# untitled.net
KiCad netlist of a schematic drawn in EAGLE
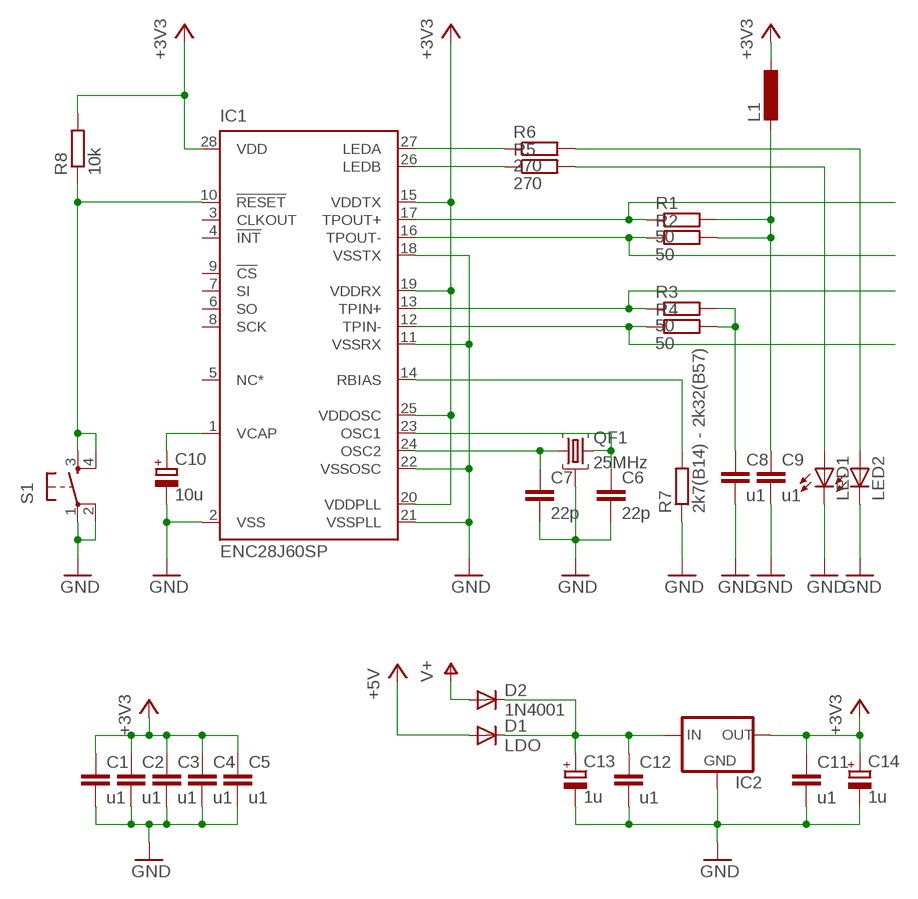
[diagram p0: schematic, sheet 1]

(export (version "E")
  (design (tool "Eeschema 10.0.6"))
  (components
    (comp (ref "C1")
      (value "u1")
      (footprint "eagle-import:C025-025X050")
      (libsource (lib "eagle-import") (part "C-EU025-025X050"))
    )
    (comp (ref "C2")
      (value "u1")
      (footprint "eagle-import:C025-025X050")
      (libsource (lib "eagle-import") (part "C-EU025-025X050"))
    )
    (comp (ref "C3")
      (value "u1")
      (footprint "eagle-import:C025-025X050")
      (libsource (lib "eagle-import") (part "C-EU025-025X050"))
    )
    (comp (ref "C4")
      (value "u1")
      (footprint "eagle-import:C025-025X050")
      (libsource (lib "eagle-import") (part "C-EU025-025X050"))
    )
    (comp (ref "C5")
      (value "u1")
      (footprint "eagle-import:C025-025X050")
      (libsource (lib "eagle-import") (part "C-EU025-025X050"))
    )
    (comp (ref "C6")
      (value "22p")
      (footprint "eagle-import:C025-025X050")
      (libsource (lib "eagle-import") (part "C-EU025-025X050"))
    )
    (comp (ref "C7")
      (value "22p")
      (footprint "eagle-import:C025-025X050")
      (libsource (lib "eagle-import") (part "C-EU025-025X050"))
    )
    (comp (ref "C8")
      (value "u1")
      (footprint "eagle-import:C025-025X050")
      (libsource (lib "eagle-import") (part "C-EU025-025X050"))
    )
    (comp (ref "C9")
      (value "u1")
      (footprint "eagle-import:C025-025X050")
      (libsource (lib "eagle-import") (part "C-EU025-025X050"))
    )
    (comp (ref "C10")
      (value "10u")
      (footprint "eagle-import:E2,5-6")
      (libsource (lib "eagle-import") (part "CPOL-EUE2.5-6"))
    )
    (comp (ref "C11")
      (value "u1")
      (footprint "eagle-import:C025-025X050")
      (libsource (lib "eagle-import") (part "C-EU025-025X050"))
    )
    (comp (ref "C12")
      (value "u1")
      (footprint "eagle-import:C025-025X050")
      (libsource (lib "eagle-import") (part "C-EU025-025X050"))
    )
    (comp (ref "C13")
      (value "1u")
      (footprint "eagle-import:E2,5-6")
      (libsource (lib "eagle-import") (part "CPOL-EUE2.5-6"))
    )
    (comp (ref "C14")
      (value "1u")
      (footprint "eagle-import:E2,5-6")
      (libsource (lib "eagle-import") (part "CPOL-EUE2.5-6"))
    )
    (comp (ref "D1")
      (value "LDO")
      (footprint "eagle-import:D-2.5")
      (libsource (lib "eagle-import") (part "DIODE-D-2.5"))
    )
    (comp (ref "D2")
      (value "1N4001")
      (footprint "eagle-import:D-2.5")
      (libsource (lib "eagle-import") (part "DIODE-D-2.5"))
    )
    (comp (ref "IC1")
      (value "ENC28J60SP")
      (footprint "eagle-import:DIL28-3")
      (fields (field (name "MF") "MICROCHIP") (field (name "MPN") "ENC28J60/SP"))
      (libsource (lib "eagle-import") (part "ENC28J60SP"))
    )
    (comp (ref "IC2")
      (value "MCP1700_TO92-INLINE")
      (footprint "eagle-import:TO92-")
      (libsource (lib "eagle-import") (part "MCP1700_TO92-INLINE"))
    )
    (comp (ref "L1")
      (value "L-EU0204/5")
      (footprint "eagle-import:0204_5")
      (libsource (lib "eagle-import") (part "L-EU0204/5"))
    )
    (comp (ref "LED1")
      (value "LED5MM")
      (footprint "eagle-import:LED5MM")
      (libsource (lib "eagle-import") (part "LED5MM"))
    )
    (comp (ref "LED2")
      (value "LED5MM")
      (footprint "eagle-import:LED5MM")
      (libsource (lib "eagle-import") (part "LED5MM"))
    )
    (comp (ref "QF1")
      (value "25MHz")
      (footprint "eagle-import:HC49U")
      (libsource (lib "eagle-import") (part "8M10AHC49T"))
    )
    (comp (ref "R1")
      (value "50")
      (footprint "eagle-import:0204_7")
      (libsource (lib "eagle-import") (part "R-EU_0204/7"))
    )
    (comp (ref "R2")
      (value "50")
      (footprint "eagle-import:0204_7")
      (libsource (lib "eagle-import") (part "R-EU_0204/7"))
    )
    (comp (ref "R3")
      (value "50")
      (footprint "eagle-import:0204_7")
      (libsource (lib "eagle-import") (part "R-EU_0204/7"))
    )
    (comp (ref "R4")
      (value "50")
      (footprint "eagle-import:0204_7")
      (libsource (lib "eagle-import") (part "R-EU_0204/7"))
    )
    (comp (ref "R5")
      (value "270")
      (footprint "eagle-import:0204_7")
      (libsource (lib "eagle-import") (part "R-EU_0204/7"))
    )
    (comp (ref "R6")
      (value "270")
      (footprint "eagle-import:0204_7")
      (libsource (lib "eagle-import") (part "R-EU_0204/7"))
    )
    (comp (ref "R7")
      (value "2k7(B14) - 2k32(B57)")
      (footprint "eagle-import:0204_7")
      (libsource (lib "eagle-import") (part "R-EU_0204/7"))
    )
    (comp (ref "R8")
      (value "10k")
      (footprint "eagle-import:0204V")
      (libsource (lib "eagle-import") (part "R-EU_0204/2V"))
    )
    (comp (ref "S1")
      (value "TAC_SWITCHPTH")
      (footprint "eagle-import:TACTILE-PTH")
      (libsource (lib "eagle-import") (part "TAC_SWITCHPTH"))
    )
  )
  (nets
    (net (code "1") (name "+3V3") (class "Default")
      (node (ref "C1") (pin "1") (pinfunction "1_1") (pintype "passive"))
      (node (ref "C11") (pin "1") (pinfunction "1_1") (pintype "passive"))
      (node (ref "C14") (pin "+") (pinfunction "+_+") (pintype "passive"))
      (node (ref "C2") (pin "1") (pinfunction "1_1") (pintype "passive"))
      (node (ref "C3") (pin "1") (pinfunction "1_1") (pintype "passive"))
      (node (ref "C4") (pin "1") (pinfunction "1_1") (pintype "passive"))
      (node (ref "C5") (pin "1") (pinfunction "1_1") (pintype "passive"))
      (node (ref "IC1") (pin "15") (pinfunction "VDDTX_15") (pintype "input"))
      (node (ref "IC1") (pin "19") (pinfunction "VDDRX_19") (pintype "input"))
      (node (ref "IC1") (pin "20") (pinfunction "VDDPLL_20") (pintype "input"))
      (node (ref "IC1") (pin "25") (pinfunction "VDDOSC_25") (pintype "input"))
      (node (ref "IC1") (pin "28") (pinfunction "VDD_28") (pintype "input"))
      (node (ref "IC2") (pin "3") (pinfunction "OUT_3") (pintype "passive"))
      (node (ref "L1") (pin "1") (pinfunction "1_1") (pintype "passive"))
      (node (ref "R8") (pin "2") (pinfunction "2_2") (pintype "passive"))
    )
    (net (code "2") (name "+5V") (class "Default")
      (node (ref "D1") (pin "A") (pinfunction "A_A") (pintype "passive"))
    )
    (net (code "3") (name "GND") (class "Default")
      (node (ref "C1") (pin "2") (pinfunction "2_2") (pintype "passive"))
      (node (ref "C10") (pin "-") (pinfunction "-_-") (pintype "passive"))
      (node (ref "C11") (pin "2") (pinfunction "2_2") (pintype "passive"))
      (node (ref "C12") (pin "2") (pinfunction "2_2") (pintype "passive"))
      (node (ref "C13") (pin "-") (pinfunction "-_-") (pintype "passive"))
      (node (ref "C14") (pin "-") (pinfunction "-_-") (pintype "passive"))
      (node (ref "C2") (pin "2") (pinfunction "2_2") (pintype "passive"))
      (node (ref "C3") (pin "2") (pinfunction "2_2") (pintype "passive"))
      (node (ref "C4") (pin "2") (pinfunction "2_2") (pintype "passive"))
      (node (ref "C5") (pin "2") (pinfunction "2_2") (pintype "passive"))
      (node (ref "C6") (pin "2") (pinfunction "2_2") (pintype "passive"))
      (node (ref "C7") (pin "2") (pinfunction "2_2") (pintype "passive"))
      (node (ref "C8") (pin "2") (pinfunction "2_2") (pintype "passive"))
      (node (ref "C9") (pin "2") (pinfunction "2_2") (pintype "passive"))
      (node (ref "IC1") (pin "11") (pinfunction "VSSRX_11") (pintype "input"))
      (node (ref "IC1") (pin "18") (pinfunction "VSSTX_18") (pintype "input"))
      (node (ref "IC1") (pin "2") (pinfunction "VSS_2") (pintype "input"))
      (node (ref "IC1") (pin "21") (pinfunction "VSSPLL_21") (pintype "input"))
      (node (ref "IC1") (pin "22") (pinfunction "VSSOSC_22") (pintype "input"))
      (node (ref "IC2") (pin "1") (pinfunction "GND_1") (pintype "input"))
      (node (ref "LED1") (pin "K") (pinfunction "C_K") (pintype "passive"))
      (node (ref "LED2") (pin "K") (pinfunction "C_K") (pintype "passive"))
      (node (ref "QF1") (pin "2") (pinfunction "2_2") (pintype "passive"))
      (node (ref "R7") (pin "1") (pinfunction "1_1") (pintype "passive"))
      (node (ref "S1") (pin "1") (pinfunction "1_1") (pintype "passive"))
      (node (ref "S1") (pin "2") (pinfunction "2_2") (pintype "passive"))
    )
    (net (code "4") (name "Net-(C8-Pad1)") (class "Default")
      (node (ref "C8") (pin "1") (pinfunction "1_1") (pintype "passive"))
      (node (ref "R3") (pin "2") (pinfunction "2_2") (pintype "passive"))
      (node (ref "R4") (pin "2") (pinfunction "2_2") (pintype "passive"))
    )
    (net (code "5") (name "Net-(C9-Pad1)") (class "Default")
      (node (ref "C9") (pin "1") (pinfunction "1_1") (pintype "passive"))
      (node (ref "L1") (pin "2") (pinfunction "2_2") (pintype "passive"))
      (node (ref "R1") (pin "2") (pinfunction "2_2") (pintype "passive"))
      (node (ref "R2") (pin "2") (pinfunction "2_2") (pintype "passive"))
    )
    (net (code "6") (name "Net-(IC1-LEDA)") (class "Default")
      (node (ref "IC1") (pin "27") (pinfunction "LEDA_27") (pintype "output"))
      (node (ref "R6") (pin "1") (pinfunction "1_1") (pintype "passive"))
    )
    (net (code "7") (name "Net-(IC1-LEDB)") (class "Default")
      (node (ref "IC1") (pin "26") (pinfunction "LEDB_26") (pintype "output"))
      (node (ref "R5") (pin "1") (pinfunction "1_1") (pintype "passive"))
    )
    (net (code "8") (name "Net-(IC1-OSC1)") (class "Default")
      (node (ref "C6") (pin "1") (pinfunction "1_1") (pintype "passive"))
      (node (ref "IC1") (pin "23") (pinfunction "OSC1_23") (pintype "input"))
      (node (ref "QF1") (pin "3") (pinfunction "3_3") (pintype "passive"))
    )
    (net (code "9") (name "Net-(IC1-OSC2)") (class "Default")
      (node (ref "C7") (pin "1") (pinfunction "1_1") (pintype "passive"))
      (node (ref "IC1") (pin "24") (pinfunction "OSC2_24") (pintype "output"))
      (node (ref "QF1") (pin "1") (pinfunction "1_1") (pintype "passive"))
    )
    (net (code "10") (name "Net-(IC1-RBIAS)") (class "Default")
      (node (ref "IC1") (pin "14") (pinfunction "RBIAS_14") (pintype "input"))
      (node (ref "R7") (pin "2") (pinfunction "2_2") (pintype "passive"))
    )
    (net (code "11") (name "Net-(IC1-TPIN+)") (class "Default")
      (node (ref "IC1") (pin "13") (pinfunction "TPIN+_13") (pintype "input"))
      (node (ref "R3") (pin "1") (pinfunction "1_1") (pintype "passive"))
    )
    (net (code "12") (name "Net-(IC1-TPIN-)") (class "Default")
      (node (ref "IC1") (pin "12") (pinfunction "TPIN-_12") (pintype "input"))
      (node (ref "R4") (pin "1") (pinfunction "1_1") (pintype "passive"))
    )
    (net (code "13") (name "Net-(IC1-TPOUT+)") (class "Default")
      (node (ref "IC1") (pin "17") (pinfunction "TPOUT+_17") (pintype "output"))
      (node (ref "R1") (pin "1") (pinfunction "1_1") (pintype "passive"))
    )
    (net (code "14") (name "Net-(IC1-TPOUT-)") (class "Default")
      (node (ref "IC1") (pin "16") (pinfunction "TPOUT-_16") (pintype "output"))
      (node (ref "R2") (pin "1") (pinfunction "1_1") (pintype "passive"))
    )
    (net (code "15") (name "Net-(IC1-VCAP)") (class "Default")
      (node (ref "C10") (pin "+") (pinfunction "+_+") (pintype "passive"))
      (node (ref "IC1") (pin "1") (pinfunction "VCAP_1") (pintype "input"))
    )
    (net (code "16") (name "Net-(IC1-~{RESET})") (class "Default")
      (node (ref "IC1") (pin "10") (pinfunction "~{RESET}_10") (pintype "input"))
      (node (ref "R8") (pin "1") (pinfunction "1_1") (pintype "passive"))
      (node (ref "S1") (pin "3") (pinfunction "3_3") (pintype "passive"))
      (node (ref "S1") (pin "4") (pinfunction "4_4") (pintype "passive"))
    )
    (net (code "17") (name "Net-(IC2-IN)") (class "Default")
      (node (ref "C12") (pin "1") (pinfunction "1_1") (pintype "passive"))
      (node (ref "C13") (pin "+") (pinfunction "+_+") (pintype "passive"))
      (node (ref "D1") (pin "C") (pinfunction "C_C") (pintype "passive"))
      (node (ref "D2") (pin "C") (pinfunction "C_C") (pintype "passive"))
      (node (ref "IC2") (pin "2") (pinfunction "IN_2") (pintype "input"))
    )
    (net (code "18") (name "Net-(LED1-PadA)") (class "Default")
      (node (ref "LED1") (pin "A") (pinfunction "A_A") (pintype "passive"))
      (node (ref "R5") (pin "2") (pinfunction "2_2") (pintype "passive"))
    )
    (net (code "19") (name "Net-(LED2-PadA)") (class "Default")
      (node (ref "LED2") (pin "A") (pinfunction "A_A") (pintype "passive"))
      (node (ref "R6") (pin "2") (pinfunction "2_2") (pintype "passive"))
    )
    (net (code "20") (name "V+") (class "Default")
      (node (ref "D2") (pin "A") (pinfunction "A_A") (pintype "passive"))
    )
    (net (code "21") (name "unconnected-(IC1-CLKOUT-Pad3)") (class "Default")
      (node (ref "IC1") (pin "3") (pinfunction "CLKOUT_3") (pintype "output"))
    )
    (net (code "22") (name "unconnected-(IC1-NC*-Pad5)") (class "Default")
      (node (ref "IC1") (pin "5") (pinfunction "NC*_5") (pintype "output"))
    )
    (net (code "23") (name "unconnected-(IC1-SCK-Pad8)") (class "Default")
      (node (ref "IC1") (pin "8") (pinfunction "SCK_8") (pintype "input"))
    )
    (net (code "24") (name "unconnected-(IC1-SI-Pad7)") (class "Default")
      (node (ref "IC1") (pin "7") (pinfunction "SI_7") (pintype "input"))
    )
    (net (code "25") (name "unconnected-(IC1-SO-Pad6)") (class "Default")
      (node (ref "IC1") (pin "6") (pinfunction "SO_6") (pintype "output"))
    )
    (net (code "26") (name "unconnected-(IC1-~{CS}-Pad9)") (class "Default")
      (node (ref "IC1") (pin "9") (pinfunction "~{CS}_9") (pintype "input"))
    )
    (net (code "27") (name "unconnected-(IC1-~{INT}-Pad4)") (class "Default")
      (node (ref "IC1") (pin "4") (pinfunction "~{INT}_4") (pintype "output"))
    )
  )
)
